# Rear_fog_lamp.net
KiCad netlist of a schematic drawn in EAGLE
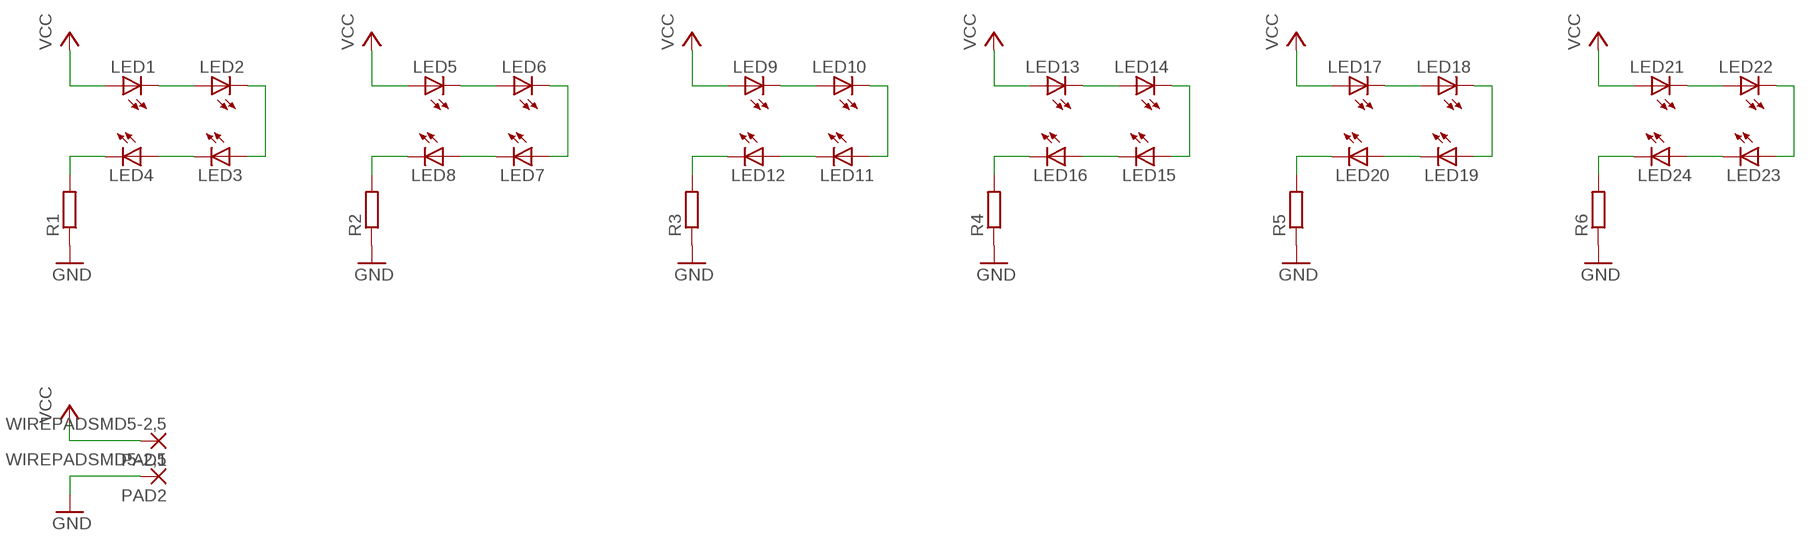
[diagram p0: schematic, sheet 1]

(export (version "E")
  (design (tool "Eeschema 10.0.6"))
  (components
    (comp (ref "LED1")
      (value "LED5MM")
      (footprint "eagle-import:LED5MM")
      (libsource (lib "eagle-import") (part "LED5MM"))
    )
    (comp (ref "LED2")
      (value "LED5MM")
      (footprint "eagle-import:LED5MM")
      (libsource (lib "eagle-import") (part "LED5MM"))
    )
    (comp (ref "LED3")
      (value "LED5MM")
      (footprint "eagle-import:LED5MM")
      (libsource (lib "eagle-import") (part "LED5MM"))
    )
    (comp (ref "LED4")
      (value "LED5MM")
      (footprint "eagle-import:LED5MM")
      (libsource (lib "eagle-import") (part "LED5MM"))
    )
    (comp (ref "LED5")
      (value "LED5MM")
      (footprint "eagle-import:LED5MM")
      (libsource (lib "eagle-import") (part "LED5MM"))
    )
    (comp (ref "LED6")
      (value "LED5MM")
      (footprint "eagle-import:LED5MM")
      (libsource (lib "eagle-import") (part "LED5MM"))
    )
    (comp (ref "LED7")
      (value "LED5MM")
      (footprint "eagle-import:LED5MM")
      (libsource (lib "eagle-import") (part "LED5MM"))
    )
    (comp (ref "LED8")
      (value "LED5MM")
      (footprint "eagle-import:LED5MM")
      (libsource (lib "eagle-import") (part "LED5MM"))
    )
    (comp (ref "LED9")
      (value "LED5MM")
      (footprint "eagle-import:LED5MM")
      (libsource (lib "eagle-import") (part "LED5MM"))
    )
    (comp (ref "LED10")
      (value "LED5MM")
      (footprint "eagle-import:LED5MM")
      (libsource (lib "eagle-import") (part "LED5MM"))
    )
    (comp (ref "LED11")
      (value "LED5MM")
      (footprint "eagle-import:LED5MM")
      (libsource (lib "eagle-import") (part "LED5MM"))
    )
    (comp (ref "LED12")
      (value "LED5MM")
      (footprint "eagle-import:LED5MM")
      (libsource (lib "eagle-import") (part "LED5MM"))
    )
    (comp (ref "LED13")
      (value "LED5MM")
      (footprint "eagle-import:LED5MM")
      (libsource (lib "eagle-import") (part "LED5MM"))
    )
    (comp (ref "LED14")
      (value "LED5MM")
      (footprint "eagle-import:LED5MM")
      (libsource (lib "eagle-import") (part "LED5MM"))
    )
    (comp (ref "LED15")
      (value "LED5MM")
      (footprint "eagle-import:LED5MM")
      (libsource (lib "eagle-import") (part "LED5MM"))
    )
    (comp (ref "LED16")
      (value "LED5MM")
      (footprint "eagle-import:LED5MM")
      (libsource (lib "eagle-import") (part "LED5MM"))
    )
    (comp (ref "LED17")
      (value "LED5MM")
      (footprint "eagle-import:LED5MM")
      (libsource (lib "eagle-import") (part "LED5MM"))
    )
    (comp (ref "LED18")
      (value "LED5MM")
      (footprint "eagle-import:LED5MM")
      (libsource (lib "eagle-import") (part "LED5MM"))
    )
    (comp (ref "LED19")
      (value "LED5MM")
      (footprint "eagle-import:LED5MM")
      (libsource (lib "eagle-import") (part "LED5MM"))
    )
    (comp (ref "LED20")
      (value "LED5MM")
      (footprint "eagle-import:LED5MM")
      (libsource (lib "eagle-import") (part "LED5MM"))
    )
    (comp (ref "LED21")
      (value "LED5MM")
      (footprint "eagle-import:LED5MM")
      (libsource (lib "eagle-import") (part "LED5MM"))
    )
    (comp (ref "LED22")
      (value "LED5MM")
      (footprint "eagle-import:LED5MM")
      (libsource (lib "eagle-import") (part "LED5MM"))
    )
    (comp (ref "LED23")
      (value "LED5MM")
      (footprint "eagle-import:LED5MM")
      (libsource (lib "eagle-import") (part "LED5MM"))
    )
    (comp (ref "LED24")
      (value "LED5MM")
      (footprint "eagle-import:LED5MM")
      (libsource (lib "eagle-import") (part "LED5MM"))
    )
    (comp (ref "PAD1")
      (value "WIREPADSMD5-2,5")
      (footprint "eagle-import:5-2,5")
      (libsource (lib "eagle-import") (part "WIREPADSMD5-2,5"))
    )
    (comp (ref "PAD2")
      (value "WIREPADSMD5-2,5")
      (footprint "eagle-import:5-2,5")
      (libsource (lib "eagle-import") (part "WIREPADSMD5-2,5"))
    )
    (comp (ref "R1")
      (value "R-EU_0204/7")
      (footprint "eagle-import:0204_7")
      (libsource (lib "eagle-import") (part "R-EU_0204/7"))
    )
    (comp (ref "R2")
      (value "R-EU_0204/7")
      (footprint "eagle-import:0204_7")
      (libsource (lib "eagle-import") (part "R-EU_0204/7"))
    )
    (comp (ref "R3")
      (value "R-EU_0204/7")
      (footprint "eagle-import:0204_7")
      (libsource (lib "eagle-import") (part "R-EU_0204/7"))
    )
    (comp (ref "R4")
      (value "R-EU_0204/7")
      (footprint "eagle-import:0204_7")
      (libsource (lib "eagle-import") (part "R-EU_0204/7"))
    )
    (comp (ref "R5")
      (value "R-EU_0204/7")
      (footprint "eagle-import:0204_7")
      (libsource (lib "eagle-import") (part "R-EU_0204/7"))
    )
    (comp (ref "R6")
      (value "R-EU_0204/7")
      (footprint "eagle-import:0204_7")
      (libsource (lib "eagle-import") (part "R-EU_0204/7"))
    )
  )
  (nets
    (net (code "1") (name "GND") (class "Default")
      (node (ref "PAD2") (pin "1") (pinfunction "P_1") (pintype "passive"))
      (node (ref "R1") (pin "1") (pinfunction "1_1") (pintype "passive"))
      (node (ref "R2") (pin "1") (pinfunction "1_1") (pintype "passive"))
      (node (ref "R3") (pin "1") (pinfunction "1_1") (pintype "passive"))
      (node (ref "R4") (pin "1") (pinfunction "1_1") (pintype "passive"))
      (node (ref "R5") (pin "1") (pinfunction "1_1") (pintype "passive"))
      (node (ref "R6") (pin "1") (pinfunction "1_1") (pintype "passive"))
    )
    (net (code "2") (name "Net-(LED1-C)") (class "Default")
      (node (ref "LED1") (pin "K") (pinfunction "C_K") (pintype "passive"))
      (node (ref "LED2") (pin "A") (pinfunction "A_A") (pintype "passive"))
    )
    (net (code "3") (name "Net-(LED2-C)") (class "Default")
      (node (ref "LED2") (pin "K") (pinfunction "C_K") (pintype "passive"))
      (node (ref "LED3") (pin "A") (pinfunction "A_A") (pintype "passive"))
    )
    (net (code "4") (name "Net-(LED3-C)") (class "Default")
      (node (ref "LED3") (pin "K") (pinfunction "C_K") (pintype "passive"))
      (node (ref "LED4") (pin "A") (pinfunction "A_A") (pintype "passive"))
    )
    (net (code "5") (name "Net-(LED4-C)") (class "Default")
      (node (ref "LED4") (pin "K") (pinfunction "C_K") (pintype "passive"))
      (node (ref "R1") (pin "2") (pinfunction "2_2") (pintype "passive"))
    )
    (net (code "6") (name "Net-(LED5-C)") (class "Default")
      (node (ref "LED5") (pin "K") (pinfunction "C_K") (pintype "passive"))
      (node (ref "LED6") (pin "A") (pinfunction "A_A") (pintype "passive"))
    )
    (net (code "7") (name "Net-(LED6-C)") (class "Default")
      (node (ref "LED6") (pin "K") (pinfunction "C_K") (pintype "passive"))
      (node (ref "LED7") (pin "A") (pinfunction "A_A") (pintype "passive"))
    )
    (net (code "8") (name "Net-(LED7-C)") (class "Default")
      (node (ref "LED7") (pin "K") (pinfunction "C_K") (pintype "passive"))
      (node (ref "LED8") (pin "A") (pinfunction "A_A") (pintype "passive"))
    )
    (net (code "9") (name "Net-(LED8-C)") (class "Default")
      (node (ref "LED8") (pin "K") (pinfunction "C_K") (pintype "passive"))
      (node (ref "R2") (pin "2") (pinfunction "2_2") (pintype "passive"))
    )
    (net (code "10") (name "Net-(LED9-C)") (class "Default")
      (node (ref "LED10") (pin "A") (pinfunction "A_A") (pintype "passive"))
      (node (ref "LED9") (pin "K") (pinfunction "C_K") (pintype "passive"))
    )
    (net (code "11") (name "Net-(LED10-C)") (class "Default")
      (node (ref "LED10") (pin "K") (pinfunction "C_K") (pintype "passive"))
      (node (ref "LED11") (pin "A") (pinfunction "A_A") (pintype "passive"))
    )
    (net (code "12") (name "Net-(LED11-C)") (class "Default")
      (node (ref "LED11") (pin "K") (pinfunction "C_K") (pintype "passive"))
      (node (ref "LED12") (pin "A") (pinfunction "A_A") (pintype "passive"))
    )
    (net (code "13") (name "Net-(LED12-C)") (class "Default")
      (node (ref "LED12") (pin "K") (pinfunction "C_K") (pintype "passive"))
      (node (ref "R3") (pin "2") (pinfunction "2_2") (pintype "passive"))
    )
    (net (code "14") (name "Net-(LED13-C)") (class "Default")
      (node (ref "LED13") (pin "K") (pinfunction "C_K") (pintype "passive"))
      (node (ref "LED14") (pin "A") (pinfunction "A_A") (pintype "passive"))
    )
    (net (code "15") (name "Net-(LED14-C)") (class "Default")
      (node (ref "LED14") (pin "K") (pinfunction "C_K") (pintype "passive"))
      (node (ref "LED15") (pin "A") (pinfunction "A_A") (pintype "passive"))
    )
    (net (code "16") (name "Net-(LED15-C)") (class "Default")
      (node (ref "LED15") (pin "K") (pinfunction "C_K") (pintype "passive"))
      (node (ref "LED16") (pin "A") (pinfunction "A_A") (pintype "passive"))
    )
    (net (code "17") (name "Net-(LED16-C)") (class "Default")
      (node (ref "LED16") (pin "K") (pinfunction "C_K") (pintype "passive"))
      (node (ref "R4") (pin "2") (pinfunction "2_2") (pintype "passive"))
    )
    (net (code "18") (name "Net-(LED17-C)") (class "Default")
      (node (ref "LED17") (pin "K") (pinfunction "C_K") (pintype "passive"))
      (node (ref "LED18") (pin "A") (pinfunction "A_A") (pintype "passive"))
    )
    (net (code "19") (name "Net-(LED18-C)") (class "Default")
      (node (ref "LED18") (pin "K") (pinfunction "C_K") (pintype "passive"))
      (node (ref "LED19") (pin "A") (pinfunction "A_A") (pintype "passive"))
    )
    (net (code "20") (name "Net-(LED19-C)") (class "Default")
      (node (ref "LED19") (pin "K") (pinfunction "C_K") (pintype "passive"))
      (node (ref "LED20") (pin "A") (pinfunction "A_A") (pintype "passive"))
    )
    (net (code "21") (name "Net-(LED20-C)") (class "Default")
      (node (ref "LED20") (pin "K") (pinfunction "C_K") (pintype "passive"))
      (node (ref "R5") (pin "2") (pinfunction "2_2") (pintype "passive"))
    )
    (net (code "22") (name "Net-(LED21-C)") (class "Default")
      (node (ref "LED21") (pin "K") (pinfunction "C_K") (pintype "passive"))
      (node (ref "LED22") (pin "A") (pinfunction "A_A") (pintype "passive"))
    )
    (net (code "23") (name "Net-(LED22-C)") (class "Default")
      (node (ref "LED22") (pin "K") (pinfunction "C_K") (pintype "passive"))
      (node (ref "LED23") (pin "A") (pinfunction "A_A") (pintype "passive"))
    )
    (net (code "24") (name "Net-(LED23-C)") (class "Default")
      (node (ref "LED23") (pin "K") (pinfunction "C_K") (pintype "passive"))
      (node (ref "LED24") (pin "A") (pinfunction "A_A") (pintype "passive"))
    )
    (net (code "25") (name "Net-(LED24-C)") (class "Default")
      (node (ref "LED24") (pin "K") (pinfunction "C_K") (pintype "passive"))
      (node (ref "R6") (pin "2") (pinfunction "2_2") (pintype "passive"))
    )
    (net (code "26") (name "VCC") (class "Default")
      (node (ref "LED1") (pin "A") (pinfunction "A_A") (pintype "passive"))
      (node (ref "LED13") (pin "A") (pinfunction "A_A") (pintype "passive"))
      (node (ref "LED17") (pin "A") (pinfunction "A_A") (pintype "passive"))
      (node (ref "LED21") (pin "A") (pinfunction "A_A") (pintype "passive"))
      (node (ref "LED5") (pin "A") (pinfunction "A_A") (pintype "passive"))
      (node (ref "LED9") (pin "A") (pinfunction "A_A") (pintype "passive"))
      (node (ref "PAD1") (pin "1") (pinfunction "P_1") (pintype "passive"))
    )
  )
)
